# digits.net
KiCad netlist of a schematic drawn in EAGLE
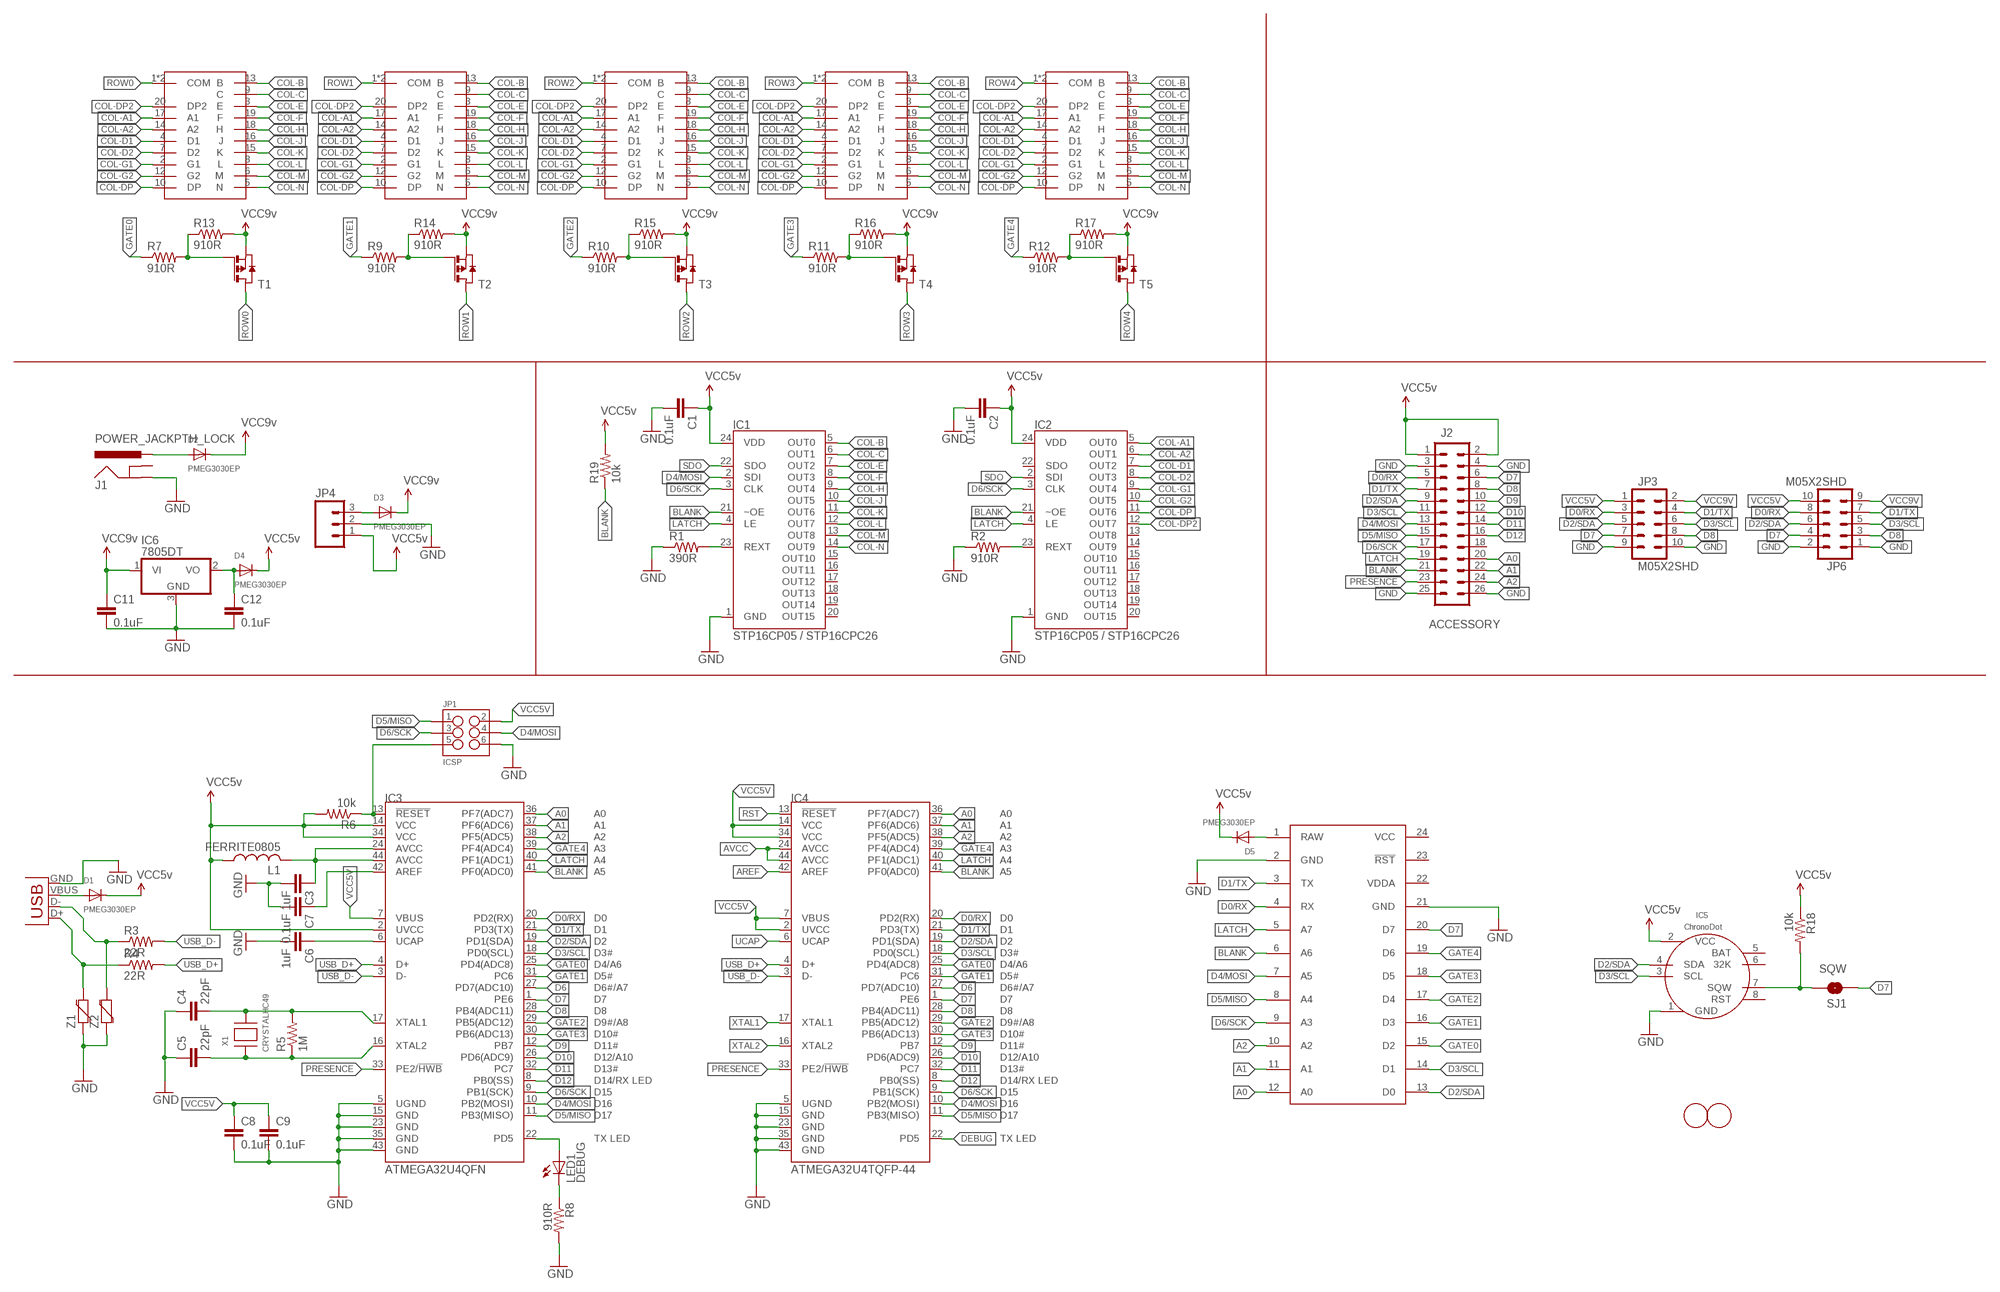
[diagram p0: schematic, sheet 1]

(export (version "E")
  (design (tool "Eeschema 10.0.6"))
  (components
    (comp (ref "C1")
      (value "0.1uF")
      (footprint "eagle-import:0805")
      (fields (field (name "PARTNO") "C0805C104K5RACTU"))
      (libsource (lib "eagle-import") (part "CAP0805"))
    )
    (comp (ref "C2")
      (value "0.1uF")
      (footprint "eagle-import:0805")
      (fields (field (name "PARTNO") "C0805C104K5RACTU"))
      (libsource (lib "eagle-import") (part "CAP0805"))
    )
    (comp (ref "C3")
      (value "1uF")
      (footprint "eagle-import:0805")
      (fields (field (name "PARTNO") "CL21B105KBFNNNE"))
      (libsource (lib "eagle-import") (part "CAP0805"))
    )
    (comp (ref "C4")
      (value "22pF")
      (footprint "eagle-import:0805")
      (fields (field (name "PARTNO") "C0805C220J5GACTU"))
      (libsource (lib "eagle-import") (part "CAP0805"))
    )
    (comp (ref "C5")
      (value "22pF")
      (footprint "eagle-import:0805")
      (fields (field (name "PARTNO") "C0805C220J5GACTU"))
      (libsource (lib "eagle-import") (part "CAP0805"))
    )
    (comp (ref "C6")
      (value "1uF")
      (footprint "eagle-import:0805")
      (fields (field (name "PARTNO") "CL21B105KBFNNNE"))
      (libsource (lib "eagle-import") (part "CAP0805"))
    )
    (comp (ref "C7")
      (value "0.1uF")
      (footprint "eagle-import:0805")
      (fields (field (name "PARTNO") "C0805C104K5RACTU"))
      (libsource (lib "eagle-import") (part "CAP0805"))
    )
    (comp (ref "C8")
      (value "0.1uF")
      (footprint "eagle-import:0805")
      (fields (field (name "PARTNO") "C0805C104K5RACTU"))
      (libsource (lib "eagle-import") (part "CAP0805"))
    )
    (comp (ref "C9")
      (value "0.1uF")
      (footprint "eagle-import:0805")
      (fields (field (name "PARTNO") "C0805C104K5RACTU"))
      (libsource (lib "eagle-import") (part "CAP0805"))
    )
    (comp (ref "C11")
      (value "0.1uF")
      (footprint "eagle-import:0805")
      (fields (field (name "PARTNO") "C0805C104K5RACTU"))
      (libsource (lib "eagle-import") (part "CAP0805"))
    )
    (comp (ref "C12")
      (value "0.1uF")
      (footprint "eagle-import:0805")
      (fields (field (name "PARTNO") "C0805C104K5RACTU"))
      (libsource (lib "eagle-import") (part "CAP0805"))
    )
    (comp (ref "CORE")
      (value "Spark Core")
      (footprint "eagle-import:SPARK_CORE")
      (libsource (lib "eagle-import") (part "SPARK_CORECORE"))
    )
    (comp (ref "D1")
      (value "PMEG3030EP")
      (footprint "eagle-import:SOD-128")
      (fields (field (name "PARTNO") "PMEG3030EP-115"))
      (libsource (lib "eagle-import") (part "DIODESOD-128"))
    )
    (comp (ref "D2")
      (value "PMEG3030EP")
      (footprint "eagle-import:SOD-128")
      (fields (field (name "PARTNO") "PMEG3030EP-115"))
      (libsource (lib "eagle-import") (part "DIODESOD-128"))
    )
    (comp (ref "D3")
      (value "PMEG3030EP")
      (footprint "eagle-import:SOD-128")
      (fields (field (name "PARTNO") "PMEG3030EP-115"))
      (libsource (lib "eagle-import") (part "DIODESOD-128"))
    )
    (comp (ref "D4")
      (value "PMEG3030EP")
      (footprint "eagle-import:SOD-128")
      (fields (field (name "PARTNO") "PMEG3030EP-115"))
      (libsource (lib "eagle-import") (part "DIODESOD-128"))
    )
    (comp (ref "D5")
      (value "PMEG3030EP")
      (footprint "eagle-import:SOD-128")
      (fields (field (name "PARTNO") "PMEG3030EP-115"))
      (libsource (lib "eagle-import") (part "DIODESOD-128"))
    )
    (comp (ref "IC1")
      (value "STP16CP05 / STP16CPC26")
      (footprint "eagle-import:SO-24DW")
      (fields (field (name "PARTNO") "STP16CPC26MTR"))
      (libsource (lib "eagle-import") (part "STP16CP05"))
    )
    (comp (ref "IC2")
      (value "STP16CP05 / STP16CPC26")
      (footprint "eagle-import:SO-24DW")
      (fields (field (name "PARTNO") "STP16CPC26MTR"))
      (libsource (lib "eagle-import") (part "STP16CP05"))
    )
    (comp (ref "IC3")
      (value "ATMEGA32U4QFN")
      (footprint "eagle-import:QFN-44")
      (fields (field (name "PARTNO") "ATMEGA32U4-MUR"))
      (libsource (lib "eagle-import") (part "ATMEGA32U4QFN"))
    )
    (comp (ref "IC4")
      (value "ATMEGA32U4TQFP-44")
      (footprint "eagle-import:TQFP44")
      (fields (field (name "PARTNO") "ATMEGA32U4-AU"))
      (libsource (lib "eagle-import") (part "ATMEGA32U4TQFP-44"))
    )
    (comp (ref "IC5")
      (value "CHRONODOT")
      (footprint "eagle-import:CHRONODOT")
      (libsource (lib "eagle-import") (part "CHRONODOT"))
    )
    (comp (ref "IC6")
      (value "7805DT")
      (footprint "eagle-import:TO252")
      (libsource (lib "eagle-import") (part "78DT05"))
    )
    (comp (ref "J1")
      (value "POWER_JACKPTH_LOCK")
      (footprint "eagle-import:POWER_JACK_PTH_LOCK")
      (fields (field (name "PARTNO") "PJ-202A"))
      (libsource (lib "eagle-import") (part "POWER_JACKPTH_LOCK"))
    )
    (comp (ref "J2")
      (value "ACCESSORY")
      (footprint "eagle-import:2X13")
      (fields (field (name "PARTNO") "SFH11-PBPC-D13-ST-BK"))
      (libsource (lib "eagle-import") (part "HEADER-M26"))
    )
    (comp (ref "JP1")
      (value "ICSP")
      (footprint "eagle-import:2X3-NS")
      (fields (field (name "PARTNO") "M20-9980346"))
      (libsource (lib "eagle-import") (part "M03X2NO_SILK"))
    )
    (comp (ref "JP2")
      (value "USBSMD")
      (footprint "eagle-import:USB-MINIB")
      (fields (field (name "PARTNO") "690-005-299-043"))
      (libsource (lib "eagle-import") (part "USBSMD"))
    )
    (comp (ref "JP3")
      (value "M05X2SHD")
      (footprint "eagle-import:2X5-SHROUDED")
      (fields (field (name "PARTNO") "302-S101"))
      (libsource (lib "eagle-import") (part "M05X2SHD"))
    )
    (comp (ref "JP4")
      (value "M03LOCK")
      (footprint "eagle-import:1X03_LOCK")
      (libsource (lib "eagle-import") (part "M03LOCK"))
    )
    (comp (ref "JP6")
      (value "M05X2SHD")
      (footprint "eagle-import:2X5-SHROUDED")
      (fields (field (name "PARTNO") "302-S101"))
      (libsource (lib "eagle-import") (part "M05X2SHD"))
    )
    (comp (ref "L1")
      (value "FERRITE0805")
      (footprint "eagle-import:0805")
      (fields (field (name "PARTNO") "CIM21J601NE"))
      (libsource (lib "eagle-import") (part "FERRITE0805"))
    )
    (comp (ref "LED1")
      (value "DEBUG")
      (footprint "eagle-import:CHIP-LED0805")
      (fields (field (name "PARTNO") "LG R971-KN-1"))
      (libsource (lib "eagle-import") (part "LEDCHIP-LED0805"))
    )
    (comp (ref "R1")
      (value "390R")
      (footprint "eagle-import:0805")
      (fields (field (name "PARTNO") "RC0805FR-07390RL"))
      (libsource (lib "eagle-import") (part "RESISTOR0805-RES"))
    )
    (comp (ref "R2")
      (value "910R")
      (footprint "eagle-import:0805")
      (fields (field (name "PARTNO") "MCR10ERTF9100"))
      (libsource (lib "eagle-import") (part "RESISTOR0805-RES"))
    )
    (comp (ref "R3")
      (value "22R")
      (footprint "eagle-import:0805")
      (fields (field (name "PARTNO") "RC0805FR-0722RL"))
      (libsource (lib "eagle-import") (part "RESISTOR0805-RES"))
    )
    (comp (ref "R4")
      (value "22R")
      (footprint "eagle-import:0805")
      (fields (field (name "PARTNO") "RC0805FR-0722RL"))
      (libsource (lib "eagle-import") (part "RESISTOR0805-RES"))
    )
    (comp (ref "R5")
      (value "1M")
      (footprint "eagle-import:0805")
      (fields (field (name "PARTNO") "RC0805FR-071ML"))
      (libsource (lib "eagle-import") (part "RESISTOR0805-RES"))
    )
    (comp (ref "R6")
      (value "10k")
      (footprint "eagle-import:0805")
      (fields (field (name "PARTNO") "RC0805JR-0710KL"))
      (libsource (lib "eagle-import") (part "RESISTOR0805-RES"))
    )
    (comp (ref "R7")
      (value "910R")
      (footprint "eagle-import:0805")
      (fields (field (name "PARTNO") "MCR10ERTF9100"))
      (libsource (lib "eagle-import") (part "RESISTOR0805-RES"))
    )
    (comp (ref "R8")
      (value "910R")
      (footprint "eagle-import:0805")
      (fields (field (name "PARTNO") "MCR10ERTF9100"))
      (libsource (lib "eagle-import") (part "RESISTOR0805-RES"))
    )
    (comp (ref "R9")
      (value "910R")
      (footprint "eagle-import:0805")
      (fields (field (name "PARTNO") "MCR10ERTF9100"))
      (libsource (lib "eagle-import") (part "RESISTOR0805-RES"))
    )
    (comp (ref "R10")
      (value "910R")
      (footprint "eagle-import:0805")
      (fields (field (name "PARTNO") "MCR10ERTF9100"))
      (libsource (lib "eagle-import") (part "RESISTOR0805-RES"))
    )
    (comp (ref "R11")
      (value "910R")
      (footprint "eagle-import:0805")
      (fields (field (name "PARTNO") "MCR10ERTF9100"))
      (libsource (lib "eagle-import") (part "RESISTOR0805-RES"))
    )
    (comp (ref "R12")
      (value "910R")
      (footprint "eagle-import:0805")
      (fields (field (name "PARTNO") "MCR10ERTF9100"))
      (libsource (lib "eagle-import") (part "RESISTOR0805-RES"))
    )
    (comp (ref "R13")
      (value "910R")
      (footprint "eagle-import:0805")
      (fields (field (name "PARTNO") "MCR10ERTF9100"))
      (libsource (lib "eagle-import") (part "RESISTOR0805-RES"))
    )
    (comp (ref "R14")
      (value "910R")
      (footprint "eagle-import:0805")
      (fields (field (name "PARTNO") "MCR10ERTF9100"))
      (libsource (lib "eagle-import") (part "RESISTOR0805-RES"))
    )
    (comp (ref "R15")
      (value "910R")
      (footprint "eagle-import:0805")
      (fields (field (name "PARTNO") "MCR10ERTF9100"))
      (libsource (lib "eagle-import") (part "RESISTOR0805-RES"))
    )
    (comp (ref "R16")
      (value "910R")
      (footprint "eagle-import:0805")
      (fields (field (name "PARTNO") "MCR10ERTF9100"))
      (libsource (lib "eagle-import") (part "RESISTOR0805-RES"))
    )
    (comp (ref "R17")
      (value "910R")
      (footprint "eagle-import:0805")
      (fields (field (name "PARTNO") "MCR10ERTF9100"))
      (libsource (lib "eagle-import") (part "RESISTOR0805-RES"))
    )
    (comp (ref "R18")
      (value "10k")
      (footprint "eagle-import:0805")
      (fields (field (name "PARTNO") "RC0805JR-0710KL"))
      (libsource (lib "eagle-import") (part "RESISTOR0805-RES"))
    )
    (comp (ref "R19")
      (value "10k")
      (footprint "eagle-import:0805")
      (libsource (lib "eagle-import") (part "RESISTOR0805-RES"))
    )
    (comp (ref "SEG1")
      (value "BL-S230X-12")
      (footprint "eagle-import:BL-S230X-12")
      (libsource (lib "eagle-import") (part "BL-S230X-12"))
    )
    (comp (ref "SEG2")
      (value "BL-S230X-12")
      (footprint "eagle-import:BL-S230X-12")
      (libsource (lib "eagle-import") (part "BL-S230X-12"))
    )
    (comp (ref "SEG3")
      (value "BL-S230X-12")
      (footprint "eagle-import:BL-S230X-12")
      (libsource (lib "eagle-import") (part "BL-S230X-12"))
    )
    (comp (ref "SEG4")
      (value "BL-S230X-12")
      (footprint "eagle-import:BL-S230X-12")
      (libsource (lib "eagle-import") (part "BL-S230X-12"))
    )
    (comp (ref "SEG5")
      (value "BL-S230X-12")
      (footprint "eagle-import:BL-S230X-12")
      (libsource (lib "eagle-import") (part "BL-S230X-12"))
    )
    (comp (ref "SJ1")
      (value "SQW")
      (footprint "eagle-import:SJ_2S-NO")
      (libsource (lib "eagle-import") (part "SOLDERJUMPERNO"))
    )
    (comp (ref "T1")
      (value "PMOSSOT23")
      (footprint "eagle-import:SOT-23")
      (fields (field (name "PARTNO") "FDN352AP"))
      (libsource (lib "eagle-import") (part "PMOSSOT23"))
    )
    (comp (ref "T2")
      (value "PMOSSOT23")
      (footprint "eagle-import:SOT-23")
      (fields (field (name "PARTNO") "FDN352AP"))
      (libsource (lib "eagle-import") (part "PMOSSOT23"))
    )
    (comp (ref "T3")
      (value "PMOSSOT23")
      (footprint "eagle-import:SOT-23")
      (fields (field (name "PARTNO") "FDN352AP"))
      (libsource (lib "eagle-import") (part "PMOSSOT23"))
    )
    (comp (ref "T4")
      (value "PMOSSOT23")
      (footprint "eagle-import:SOT-23")
      (fields (field (name "PARTNO") "FDN352AP"))
      (libsource (lib "eagle-import") (part "PMOSSOT23"))
    )
    (comp (ref "T5")
      (value "PMOSSOT23")
      (footprint "eagle-import:SOT-23")
      (fields (field (name "PARTNO") "FDN352AP"))
      (libsource (lib "eagle-import") (part "PMOSSOT23"))
    )
    (comp (ref "U$1")
      (value "FIDUCIAL")
      (footprint "eagle-import:FIDUCIAL_1MM")
      (libsource (lib "eagle-import") (part "FIDUCIAL"))
    )
    (comp (ref "U$2")
      (value "FIDUCIAL")
      (footprint "eagle-import:FIDUCIAL_1MM")
      (libsource (lib "eagle-import") (part "FIDUCIAL"))
    )
    (comp (ref "X1")
      (value "CRYSTALHC49")
      (footprint "eagle-import:HC49")
      (fields (field (name "PARTNO") "9C-16.000MAAJ-T"))
      (libsource (lib "eagle-import") (part "CRYSTALHC49"))
    )
    (comp (ref "Z1")
      (value "VARISTOR-0603")
      (footprint "eagle-import:0603-RES")
      (fields (field (name "PARTNO") "CG0603MLC-05E"))
      (libsource (lib "eagle-import") (part "VARISTOR-0603"))
    )
    (comp (ref "Z2")
      (value "VARISTOR-0603")
      (footprint "eagle-import:0603-RES")
      (fields (field (name "PARTNO") "CG0603MLC-05E"))
      (libsource (lib "eagle-import") (part "VARISTOR-0603"))
    )
  )
  (nets
    (net (code "1") (name "/VCC") (class "Default")
      (node (ref "CORE") (pin "24") (pinfunction "VCC_24") (pintype "power_in"))
    )
    (net (code "2") (name "/VDDA") (class "Default")
      (node (ref "CORE") (pin "22") (pinfunction "VDDA_22") (pintype "power_in"))
    )
    (net (code "3") (name "A0") (class "Default")
      (node (ref "CORE") (pin "12") (pinfunction "A0_12") (pintype "bidirectional"))
      (node (ref "IC3") (pin "36") (pinfunction "PF7(ADC7)_36") (pintype "bidirectional"))
      (node (ref "IC4") (pin "36") (pinfunction "PF7(ADC7)_36") (pintype "bidirectional"))
      (node (ref "J2") (pin "20") (pinfunction "20_20") (pintype "passive"))
    )
    (net (code "4") (name "A1") (class "Default")
      (node (ref "CORE") (pin "11") (pinfunction "A1_11") (pintype "bidirectional"))
      (node (ref "IC3") (pin "37") (pinfunction "PF6(ADC6)_37") (pintype "bidirectional"))
      (node (ref "IC4") (pin "37") (pinfunction "PF6(ADC6)_37") (pintype "bidirectional"))
      (node (ref "J2") (pin "22") (pinfunction "22_22") (pintype "passive"))
    )
    (net (code "5") (name "A2") (class "Default")
      (node (ref "CORE") (pin "10") (pinfunction "A2_10") (pintype "bidirectional"))
      (node (ref "IC3") (pin "38") (pinfunction "PF5(ADC5)_38") (pintype "bidirectional"))
      (node (ref "IC4") (pin "38") (pinfunction "PF5(ADC5)_38") (pintype "bidirectional"))
      (node (ref "J2") (pin "24") (pinfunction "24_24") (pintype "passive"))
    )
    (net (code "6") (name "AREF") (class "Default")
      (node (ref "C7") (pin "1") (pinfunction "1_1") (pintype "passive"))
      (node (ref "IC3") (pin "42") (pinfunction "AREF_42") (pintype "bidirectional"))
      (node (ref "IC4") (pin "42") (pinfunction "AREF_42") (pintype "bidirectional"))
    )
    (net (code "7") (name "AVCC") (class "Default")
      (node (ref "C3") (pin "1") (pinfunction "1_1") (pintype "passive"))
      (node (ref "IC3") (pin "24") (pinfunction "AVCC_24") (pintype "bidirectional"))
      (node (ref "IC3") (pin "44") (pinfunction "AVCC_44") (pintype "bidirectional"))
      (node (ref "IC4") (pin "24") (pinfunction "AVCC_24") (pintype "bidirectional"))
      (node (ref "IC4") (pin "44") (pinfunction "AVCC_44") (pintype "bidirectional"))
      (node (ref "L1") (pin "2") (pinfunction "2_2") (pintype "passive"))
    )
    (net (code "8") (name "BLANK") (class "Default")
      (node (ref "CORE") (pin "6") (pinfunction "A6_6") (pintype "bidirectional"))
      (node (ref "IC1") (pin "21") (pinfunction "~{OE}_21") (pintype "bidirectional"))
      (node (ref "IC2") (pin "21") (pinfunction "~{OE}_21") (pintype "bidirectional"))
      (node (ref "IC3") (pin "41") (pinfunction "PF0(ADC0)_41") (pintype "bidirectional"))
      (node (ref "IC4") (pin "41") (pinfunction "PF0(ADC0)_41") (pintype "bidirectional"))
      (node (ref "J2") (pin "21") (pinfunction "21_21") (pintype "passive"))
      (node (ref "R19") (pin "1") (pinfunction "1_1") (pintype "passive"))
    )
    (net (code "9") (name "COL-A1") (class "Default")
      (node (ref "IC2") (pin "5") (pinfunction "OUT0_5") (pintype "bidirectional"))
      (node (ref "SEG1") (pin "17") (pinfunction "A1_17") (pintype "bidirectional"))
      (node (ref "SEG2") (pin "17") (pinfunction "A1_17") (pintype "bidirectional"))
      (node (ref "SEG3") (pin "17") (pinfunction "A1_17") (pintype "bidirectional"))
      (node (ref "SEG4") (pin "17") (pinfunction "A1_17") (pintype "bidirectional"))
      (node (ref "SEG5") (pin "17") (pinfunction "A1_17") (pintype "bidirectional"))
    )
    (net (code "10") (name "COL-A2") (class "Default")
      (node (ref "IC2") (pin "6") (pinfunction "OUT1_6") (pintype "bidirectional"))
      (node (ref "SEG1") (pin "14") (pinfunction "A2_14") (pintype "bidirectional"))
      (node (ref "SEG2") (pin "14") (pinfunction "A2_14") (pintype "bidirectional"))
      (node (ref "SEG3") (pin "14") (pinfunction "A2_14") (pintype "bidirectional"))
      (node (ref "SEG4") (pin "14") (pinfunction "A2_14") (pintype "bidirectional"))
      (node (ref "SEG5") (pin "14") (pinfunction "A2_14") (pintype "bidirectional"))
    )
    (net (code "11") (name "COL-B") (class "Default")
      (node (ref "IC1") (pin "5") (pinfunction "OUT0_5") (pintype "bidirectional"))
      (node (ref "SEG1") (pin "13") (pinfunction "B_13") (pintype "bidirectional"))
      (node (ref "SEG2") (pin "13") (pinfunction "B_13") (pintype "bidirectional"))
      (node (ref "SEG3") (pin "13") (pinfunction "B_13") (pintype "bidirectional"))
      (node (ref "SEG4") (pin "13") (pinfunction "B_13") (pintype "bidirectional"))
      (node (ref "SEG5") (pin "13") (pinfunction "B_13") (pintype "bidirectional"))
    )
    (net (code "12") (name "COL-C") (class "Default")
      (node (ref "IC1") (pin "6") (pinfunction "OUT1_6") (pintype "bidirectional"))
      (node (ref "SEG1") (pin "9") (pinfunction "C_9") (pintype "bidirectional"))
      (node (ref "SEG2") (pin "9") (pinfunction "C_9") (pintype "bidirectional"))
      (node (ref "SEG3") (pin "9") (pinfunction "C_9") (pintype "bidirectional"))
      (node (ref "SEG4") (pin "9") (pinfunction "C_9") (pintype "bidirectional"))
      (node (ref "SEG5") (pin "9") (pinfunction "C_9") (pintype "bidirectional"))
    )
    (net (code "13") (name "COL-D1") (class "Default")
      (node (ref "IC2") (pin "7") (pinfunction "OUT2_7") (pintype "bidirectional"))
      (node (ref "SEG1") (pin "4") (pinfunction "D1_4") (pintype "bidirectional"))
      (node (ref "SEG2") (pin "4") (pinfunction "D1_4") (pintype "bidirectional"))
      (node (ref "SEG3") (pin "4") (pinfunction "D1_4") (pintype "bidirectional"))
      (node (ref "SEG4") (pin "4") (pinfunction "D1_4") (pintype "bidirectional"))
      (node (ref "SEG5") (pin "4") (pinfunction "D1_4") (pintype "bidirectional"))
    )
    (net (code "14") (name "COL-D2") (class "Default")
      (node (ref "IC2") (pin "8") (pinfunction "OUT3_8") (pintype "bidirectional"))
      (node (ref "SEG1") (pin "7") (pinfunction "D2_7") (pintype "bidirectional"))
      (node (ref "SEG2") (pin "7") (pinfunction "D2_7") (pintype "bidirectional"))
      (node (ref "SEG3") (pin "7") (pinfunction "D2_7") (pintype "bidirectional"))
      (node (ref "SEG4") (pin "7") (pinfunction "D2_7") (pintype "bidirectional"))
      (node (ref "SEG5") (pin "7") (pinfunction "D2_7") (pintype "bidirectional"))
    )
    (net (code "15") (name "COL-DP") (class "Default")
      (node (ref "IC2") (pin "11") (pinfunction "OUT6_11") (pintype "bidirectional"))
      (node (ref "SEG1") (pin "10") (pinfunction "DP_10") (pintype "bidirectional"))
      (node (ref "SEG2") (pin "10") (pinfunction "DP_10") (pintype "bidirectional"))
      (node (ref "SEG3") (pin "10") (pinfunction "DP_10") (pintype "bidirectional"))
      (node (ref "SEG4") (pin "10") (pinfunction "DP_10") (pintype "bidirectional"))
      (node (ref "SEG5") (pin "10") (pinfunction "DP_10") (pintype "bidirectional"))
    )
    (net (code "16") (name "COL-DP2") (class "Default")
      (node (ref "IC2") (pin "12") (pinfunction "OUT7_12") (pintype "bidirectional"))
      (node (ref "SEG1") (pin "20") (pinfunction "DP2_20") (pintype "bidirectional"))
      (node (ref "SEG2") (pin "20") (pinfunction "DP2_20") (pintype "bidirectional"))
      (node (ref "SEG3") (pin "20") (pinfunction "DP2_20") (pintype "bidirectional"))
      (node (ref "SEG4") (pin "20") (pinfunction "DP2_20") (pintype "bidirectional"))
      (node (ref "SEG5") (pin "20") (pinfunction "DP2_20") (pintype "bidirectional"))
    )
    (net (code "17") (name "COL-E") (class "Default")
      (node (ref "IC1") (pin "7") (pinfunction "OUT2_7") (pintype "bidirectional"))
      (node (ref "SEG1") (pin "3") (pinfunction "E_3") (pintype "bidirectional"))
      (node (ref "SEG2") (pin "3") (pinfunction "E_3") (pintype "bidirectional"))
      (node (ref "SEG3") (pin "3") (pinfunction "E_3") (pintype "bidirectional"))
      (node (ref "SEG4") (pin "3") (pinfunction "E_3") (pintype "bidirectional"))
      (node (ref "SEG5") (pin "3") (pinfunction "E_3") (pintype "bidirectional"))
    )
    (net (code "18") (name "COL-F") (class "Default")
      (node (ref "IC1") (pin "8") (pinfunction "OUT3_8") (pintype "bidirectional"))
      (node (ref "SEG1") (pin "19") (pinfunction "F_19") (pintype "bidirectional"))
      (node (ref "SEG2") (pin "19") (pinfunction "F_19") (pintype "bidirectional"))
      (node (ref "SEG3") (pin "19") (pinfunction "F_19") (pintype "bidirectional"))
      (node (ref "SEG4") (pin "19") (pinfunction "F_19") (pintype "bidirectional"))
      (node (ref "SEG5") (pin "19") (pinfunction "F_19") (pintype "bidirectional"))
    )
    (net (code "19") (name "COL-G1") (class "Default")
      (node (ref "IC2") (pin "9") (pinfunction "OUT4_9") (pintype "bidirectional"))
      (node (ref "SEG1") (pin "2") (pinfunction "G1_2") (pintype "bidirectional"))
      (node (ref "SEG2") (pin "2") (pinfunction "G1_2") (pintype "bidirectional"))
      (node (ref "SEG3") (pin "2") (pinfunction "G1_2") (pintype "bidirectional"))
      (node (ref "SEG4") (pin "2") (pinfunction "G1_2") (pintype "bidirectional"))
      (node (ref "SEG5") (pin "2") (pinfunction "G1_2") (pintype "bidirectional"))
    )
    (net (code "20") (name "COL-G2") (class "Default")
      (node (ref "IC2") (pin "10") (pinfunction "OUT5_10") (pintype "bidirectional"))
      (node (ref "SEG1") (pin "12") (pinfunction "G2_12") (pintype "bidirectional"))
      (node (ref "SEG2") (pin "12") (pinfunction "G2_12") (pintype "bidirectional"))
      (node (ref "SEG3") (pin "12") (pinfunction "G2_12") (pintype "bidirectional"))
      (node (ref "SEG4") (pin "12") (pinfunction "G2_12") (pintype "bidirectional"))
      (node (ref "SEG5") (pin "12") (pinfunction "G2_12") (pintype "bidirectional"))
    )
    (net (code "21") (name "COL-H") (class "Default")
      (node (ref "IC1") (pin "9") (pinfunction "OUT4_9") (pintype "bidirectional"))
      (node (ref "SEG1") (pin "18") (pinfunction "H_18") (pintype "bidirectional"))
      (node (ref "SEG2") (pin "18") (pinfunction "H_18") (pintype "bidirectional"))
      (node (ref "SEG3") (pin "18") (pinfunction "H_18") (pintype "bidirectional"))
      (node (ref "SEG4") (pin "18") (pinfunction "H_18") (pintype "bidirectional"))
      (node (ref "SEG5") (pin "18") (pinfunction "H_18") (pintype "bidirectional"))
    )
    (net (code "22") (name "COL-J") (class "Default")
      (node (ref "IC1") (pin "10") (pinfunction "OUT5_10") (pintype "bidirectional"))
      (node (ref "SEG1") (pin "16") (pinfunction "J_16") (pintype "bidirectional"))
      (node (ref "SEG2") (pin "16") (pinfunction "J_16") (pintype "bidirectional"))
      (node (ref "SEG3") (pin "16") (pinfunction "J_16") (pintype "bidirectional"))
      (node (ref "SEG4") (pin "16") (pinfunction "J_16") (pintype "bidirectional"))
      (node (ref "SEG5") (pin "16") (pinfunction "J_16") (pintype "bidirectional"))
    )
    (net (code "23") (name "COL-K") (class "Default")
      (node (ref "IC1") (pin "11") (pinfunction "OUT6_11") (pintype "bidirectional"))
      (node (ref "SEG1") (pin "15") (pinfunction "K_15") (pintype "bidirectional"))
      (node (ref "SEG2") (pin "15") (pinfunction "K_15") (pintype "bidirectional"))
      (node (ref "SEG3") (pin "15") (pinfunction "K_15") (pintype "bidirectional"))
      (node (ref "SEG4") (pin "15") (pinfunction "K_15") (pintype "bidirectional"))
      (node (ref "SEG5") (pin "15") (pinfunction "K_15") (pintype "bidirectional"))
    )
    (net (code "24") (name "COL-L") (class "Default")
      (node (ref "IC1") (pin "12") (pinfunction "OUT7_12") (pintype "bidirectional"))
      (node (ref "SEG1") (pin "8") (pinfunction "L_8") (pintype "bidirectional"))
      (node (ref "SEG2") (pin "8") (pinfunction "L_8") (pintype "bidirectional"))
      (node (ref "SEG3") (pin "8") (pinfunction "L_8") (pintype "bidirectional"))
      (node (ref "SEG4") (pin "8") (pinfunction "L_8") (pintype "bidirectional"))
      (node (ref "SEG5") (pin "8") (pinfunction "L_8") (pintype "bidirectional"))
    )
    (net (code "25") (name "COL-M") (class "Default")
      (node (ref "IC1") (pin "13") (pinfunction "OUT8_13") (pintype "bidirectional"))
      (node (ref "SEG1") (pin "6") (pinfunction "M_6") (pintype "bidirectional"))
      (node (ref "SEG2") (pin "6") (pinfunction "M_6") (pintype "bidirectional"))
      (node (ref "SEG3") (pin "6") (pinfunction "M_6") (pintype "bidirectional"))
      (node (ref "SEG4") (pin "6") (pinfunction "M_6") (pintype "bidirectional"))
      (node (ref "SEG5") (pin "6") (pinfunction "M_6") (pintype "bidirectional"))
    )
    (net (code "26") (name "COL-N") (class "Default")
      (node (ref "IC1") (pin "14") (pinfunction "OUT9_14") (pintype "bidirectional"))
      (node (ref "SEG1") (pin "5") (pinfunction "N_5") (pintype "bidirectional"))
      (node (ref "SEG2") (pin "5") (pinfunction "N_5") (pintype "bidirectional"))
      (node (ref "SEG3") (pin "5") (pinfunction "N_5") (pintype "bidirectional"))
      (node (ref "SEG4") (pin "5") (pinfunction "N_5") (pintype "bidirectional"))
      (node (ref "SEG5") (pin "5") (pinfunction "N_5") (pintype "bidirectional"))
    )
    (net (code "27") (name "D0{slash}RX") (class "Default")
      (node (ref "CORE") (pin "4") (pinfunction "RX_4") (pintype "bidirectional"))
      (node (ref "IC3") (pin "20") (pinfunction "PD2(RX)_20") (pintype "bidirectional"))
      (node (ref "IC4") (pin "20") (pinfunction "PD2(RX)_20") (pintype "bidirectional"))
      (node (ref "J2") (pin "5") (pinfunction "5_5") (pintype "passive"))
      (node (ref "JP3") (pin "3") (pinfunction "3_3") (pintype "passive"))
      (node (ref "JP6") (pin "8") (pinfunction "8_8") (pintype "passive"))
    )
    (net (code "28") (name "D1{slash}TX") (class "Default")
      (node (ref "CORE") (pin "3") (pinfunction "TX_3") (pintype "bidirectional"))
      (node (ref "IC3") (pin "21") (pinfunction "PD3(TX)_21") (pintype "bidirectional"))
      (node (ref "IC4") (pin "21") (pinfunction "PD3(TX)_21") (pintype "bidirectional"))
      (node (ref "J2") (pin "7") (pinfunction "7_7") (pintype "passive"))
      (node (ref "JP3") (pin "4") (pinfunction "4_4") (pintype "passive"))
      (node (ref "JP6") (pin "7") (pinfunction "7_7") (pintype "passive"))
    )
    (net (code "29") (name "D2{slash}SDA") (class "Default")
      (node (ref "CORE") (pin "13") (pinfunction "D0_13") (pintype "bidirectional"))
      (node (ref "IC3") (pin "19") (pinfunction "PD1(SDA)_19") (pintype "bidirectional"))
      (node (ref "IC4") (pin "19") (pinfunction "PD1(SDA)_19") (pintype "bidirectional"))
      (node (ref "IC5") (pin "4") (pinfunction "SDA_4") (pintype "bidirectional"))
      (node (ref "J2") (pin "9") (pinfunction "9_9") (pintype "passive"))
      (node (ref "JP3") (pin "5") (pinfunction "5_5") (pintype "passive"))
      (node (ref "JP6") (pin "6") (pinfunction "6_6") (pintype "passive"))
    )
    (net (code "30") (name "D3{slash}SCL") (class "Default")
      (node (ref "CORE") (pin "14") (pinfunction "D1_14") (pintype "bidirectional"))
      (node (ref "IC3") (pin "18") (pinfunction "PD0(SCL)_18") (pintype "bidirectional"))
      (node (ref "IC4") (pin "18") (pinfunction "PD0(SCL)_18") (pintype "bidirectional"))
      (node (ref "IC5") (pin "3") (pinfunction "SCL_3") (pintype "bidirectional"))
      (node (ref "J2") (pin "11") (pinfunction "11_11") (pintype "passive"))
      (node (ref "JP3") (pin "6") (pinfunction "6_6") (pintype "passive"))
      (node (ref "JP6") (pin "5") (pinfunction "5_5") (pintype "passive"))
    )
    (net (code "31") (name "D4{slash}MOSI") (class "Default")
      (node (ref "CORE") (pin "7") (pinfunction "A5_7") (pintype "bidirectional"))
      (node (ref "IC1") (pin "2") (pinfunction "SDI_2") (pintype "bidirectional"))
      (node (ref "IC3") (pin "10") (pinfunction "PB2(MOSI)_10") (pintype "bidirectional"))
      (node (ref "IC4") (pin "10") (pinfunction "PB2(MOSI)_10") (pintype "bidirectional"))
      (node (ref "J2") (pin "13") (pinfunction "13_13") (pintype "passive"))
      (node (ref "JP1") (pin "4") (pinfunction "4_4") (pintype "bidirectional"))
    )
    (net (code "32") (name "D5{slash}MISO") (class "Default")
      (node (ref "CORE") (pin "8") (pinfunction "A4_8") (pintype "bidirectional"))
      (node (ref "IC3") (pin "11") (pinfunction "PB3(MISO)_11") (pintype "bidirectional"))
      (node (ref "IC4") (pin "11") (pinfunction "PB3(MISO)_11") (pintype "bidirectional"))
      (node (ref "J2") (pin "15") (pinfunction "15_15") (pintype "passive"))
      (node (ref "JP1") (pin "1") (pinfunction "1_1") (pintype "bidirectional"))
    )
    (net (code "33") (name "D6") (class "Default")
      (node (ref "IC3") (pin "27") (pinfunction "PD7(ADC10)_27") (pintype "bidirectional"))
      (node (ref "IC4") (pin "27") (pinfunction "PD7(ADC10)_27") (pintype "bidirectional"))
    )
    (net (code "34") (name "D6{slash}SCK") (class "Default")
      (node (ref "CORE") (pin "9") (pinfunction "A3_9") (pintype "bidirectional"))
      (node (ref "IC1") (pin "3") (pinfunction "CLK_3") (pintype "bidirectional"))
      (node (ref "IC2") (pin "3") (pinfunction "CLK_3") (pintype "bidirectional"))
      (node (ref "IC3") (pin "9") (pinfunction "PB1(SCK)_9") (pintype "bidirectional"))
      (node (ref "IC4") (pin "9") (pinfunction "PB1(SCK)_9") (pintype "bidirectional"))
      (node (ref "J2") (pin "17") (pinfunction "17_17") (pintype "passive"))
      (node (ref "JP1") (pin "3") (pinfunction "3_3") (pintype "bidirectional"))
    )
    (net (code "35") (name "D7") (class "Default")
      (node (ref "CORE") (pin "20") (pinfunction "D7_20") (pintype "bidirectional"))
      (node (ref "IC3") (pin "1") (pinfunction "PE6_1") (pintype "bidirectional"))
      (node (ref "IC4") (pin "1") (pinfunction "PE6_1") (pintype "bidirectional"))
      (node (ref "J2") (pin "6") (pinfunction "6_6") (pintype "passive"))
      (node (ref "JP3") (pin "7") (pinfunction "7_7") (pintype "passive"))
      (node (ref "JP6") (pin "4") (pinfunction "4_4") (pintype "passive"))
      (node (ref "SJ1") (pin "1") (pinfunction "1_1") (pintype "passive"))
    )
    (net (code "36") (name "D8") (class "Default")
      (node (ref "IC3") (pin "28") (pinfunction "PB4(ADC11)_28") (pintype "bidirectional"))
      (node (ref "IC4") (pin "28") (pinfunction "PB4(ADC11)_28") (pintype "bidirectional"))
      (node (ref "J2") (pin "8") (pinfunction "8_8") (pintype "passive"))
      (node (ref "JP3") (pin "8") (pinfunction "8_8") (pintype "passive"))
      (node (ref "JP6") (pin "3") (pinfunction "3_3") (pintype "passive"))
    )
    (net (code "37") (name "D9") (class "Default")
      (node (ref "IC3") (pin "12") (pinfunction "PB7_12") (pintype "bidirectional"))
      (node (ref "IC4") (pin "12") (pinfunction "PB7_12") (pintype "bidirectional"))
      (node (ref "J2") (pin "10") (pinfunction "10_10") (pintype "passive"))
    )
    (net (code "38") (name "D10") (class "Default")
      (node (ref "IC3") (pin "26") (pinfunction "PD6(ADC9)_26") (pintype "bidirectional"))
      (node (ref "IC4") (pin "26") (pinfunction "PD6(ADC9)_26") (pintype "bidirectional"))
      (node (ref "J2") (pin "12") (pinfunction "12_12") (pintype "passive"))
    )
    (net (code "39") (name "D11") (class "Default")
      (node (ref "IC3") (pin "32") (pinfunction "PC7_32") (pintype "bidirectional"))
      (node (ref "IC4") (pin "32") (pinfunction "PC7_32") (pintype "bidirectional"))
      (node (ref "J2") (pin "14") (pinfunction "14_14") (pintype "passive"))
    )
    (net (code "40") (name "D12") (class "Default")
      (node (ref "IC3") (pin "8") (pinfunction "PB0(SS)_8") (pintype "bidirectional"))
      (node (ref "IC4") (pin "8") (pinfunction "PB0(SS)_8") (pintype "bidirectional"))
      (node (ref "J2") (pin "16") (pinfunction "16_16") (pintype "passive"))
    )
    (net (code "41") (name "DEBUG") (class "Default")
      (node (ref "IC3") (pin "22") (pinfunction "PD5_22") (pintype "bidirectional"))
      (node (ref "IC4") (pin "22") (pinfunction "PD5_22") (pintype "bidirectional"))
      (node (ref "LED1") (pin "A") (pinfunction "A_A") (pintype "passive"))
    )
    (net (code "42") (name "GATE0") (class "Default")
      (node (ref "CORE") (pin "15") (pinfunction "D2_15") (pintype "bidirectional"))
      (node (ref "IC3") (pin "25") (pinfunction "PD4(ADC8)_25") (pintype "bidirectional"))
      (node (ref "IC4") (pin "25") (pinfunction "PD4(ADC8)_25") (pintype "bidirectional"))
      (node (ref "R7") (pin "1") (pinfunction "1_1") (pintype "passive"))
    )
    (net (code "43") (name "GATE1") (class "Default")
      (node (ref "CORE") (pin "16") (pinfunction "D3_16") (pintype "bidirectional"))
      (node (ref "IC3") (pin "31") (pinfunction "PC6_31") (pintype "bidirectional"))
      (node (ref "IC4") (pin "31") (pinfunction "PC6_31") (pintype "bidirectional"))
      (node (ref "R9") (pin "1") (pinfunction "1_1") (pintype "passive"))
    )
    (net (code "44") (name "GATE2") (class "Default")
      (node (ref "CORE") (pin "17") (pinfunction "D4_17") (pintype "bidirectional"))
      (node (ref "IC3") (pin "29") (pinfunction "PB5(ADC12)_29") (pintype "bidirectional"))
      (node (ref "IC4") (pin "29") (pinfunction "PB5(ADC12)_29") (pintype "bidirectional"))
      (node (ref "R10") (pin "1") (pinfunction "1_1") (pintype "passive"))
    )
    (net (code "45") (name "GATE3") (class "Default")
      (node (ref "CORE") (pin "18") (pinfunction "D5_18") (pintype "bidirectional"))
      (node (ref "IC3") (pin "30") (pinfunction "PB6(ADC13)_30") (pintype "bidirectional"))
      (node (ref "IC4") (pin "30") (pinfunction "PB6(ADC13)_30") (pintype "bidirectional"))
      (node (ref "R11") (pin "1") (pinfunction "1_1") (pintype "passive"))
    )
    (net (code "46") (name "GATE4") (class "Default")
      (node (ref "CORE") (pin "19") (pinfunction "D6_19") (pintype "bidirectional"))
      (node (ref "IC3") (pin "39") (pinfunction "PF4(ADC4)_39") (pintype "bidirectional"))
      (node (ref "IC4") (pin "39") (pinfunction "PF4(ADC4)_39") (pintype "bidirectional"))
      (node (ref "R12") (pin "1") (pinfunction "1_1") (pintype "passive"))
    )
    (net (code "47") (name "GND") (class "Default")
      (node (ref "C1") (pin "2") (pinfunction "2_2") (pintype "passive"))
      (node (ref "C11") (pin "2") (pinfunction "2_2") (pintype "passive"))
      (node (ref "C12") (pin "2") (pinfunction "2_2") (pintype "passive"))
      (node (ref "C2") (pin "2") (pinfunction "2_2") (pintype "passive"))
      (node (ref "C3") (pin "2") (pinfunction "2_2") (pintype "passive"))
      (node (ref "C4") (pin "1") (pinfunction "1_1") (pintype "passive"))
      (node (ref "C5") (pin "1") (pinfunction "1_1") (pintype "passive"))
      (node (ref "C6") (pin "2") (pinfunction "2_2") (pintype "passive"))
      (node (ref "C7") (pin "2") (pinfunction "2_2") (pintype "passive"))
      (node (ref "C8") (pin "2") (pinfunction "2_2") (pintype "passive"))
      (node (ref "C9") (pin "2") (pinfunction "2_2") (pintype "passive"))
      (node (ref "CORE") (pin "2") (pinfunction "GND_2") (pintype "power_in"))
      (node (ref "CORE") (pin "21") (pinfunction "GND_21") (pintype "power_in"))
      (node (ref "IC1") (pin "1") (pinfunction "GND_1") (pintype "bidirectional"))
      (node (ref "IC2") (pin "1") (pinfunction "GND_1") (pintype "bidirectional"))
      (node (ref "IC3") (pin "15") (pinfunction "GND_15") (pintype "bidirectional"))
      (node (ref "IC3") (pin "23") (pinfunction "GND_23") (pintype "bidirectional"))
      (node (ref "IC3") (pin "35") (pinfunction "GND_35") (pintype "bidirectional"))
      (node (ref "IC3") (pin "43") (pinfunction "GND_43") (pintype "bidirectional"))
      (node (ref "IC3") (pin "5") (pinfunction "UGND_5") (pintype "bidirectional"))
      (node (ref "IC4") (pin "15") (pinfunction "GND_15") (pintype "bidirectional"))
      (node (ref "IC4") (pin "23") (pinfunction "GND_23") (pintype "bidirectional"))
      (node (ref "IC4") (pin "35") (pinfunction "GND_35") (pintype "bidirectional"))
      (node (ref "IC4") (pin "43") (pinfunction "GND_43") (pintype "bidirectional"))
      (node (ref "IC4") (pin "5") (pinfunction "UGND_5") (pintype "bidirectional"))
      (node (ref "IC5") (pin "1") (pinfunction "GND_1") (pintype "bidirectional"))
      (node (ref "IC6") (pin "3") (pinfunction "GND_3") (pintype "passive"))
      (node (ref "J1") (pin "GND") (pinfunction "GND_GND") (pintype "bidirectional"))
      (node (ref "J2") (pin "25") (pinfunction "25_25") (pintype "passive"))
      (node (ref "J2") (pin "26") (pinfunction "26_26") (pintype "passive"))
      (node (ref "J2") (pin "3") (pinfunction "3_3") (pintype "passive"))
      (node (ref "J2") (pin "4") (pinfunction "4_4") (pintype "passive"))
      (node (ref "JP1") (pin "6") (pinfunction "6_6") (pintype "bidirectional"))
      (node (ref "JP2") (pin "GND") (pinfunction "GND_GND") (pintype "bidirectional"))
      (node (ref "JP3") (pin "10") (pinfunction "10_10") (pintype "passive"))
      (node (ref "JP3") (pin "9") (pinfunction "9_9") (pintype "passive"))
      (node (ref "JP4") (pin "2") (pinfunction "2_2") (pintype "passive"))
      (node (ref "JP6") (pin "1") (pinfunction "1_1") (pintype "passive"))
      (node (ref "JP6") (pin "2") (pinfunction "2_2") (pintype "passive"))
      (node (ref "R1") (pin "1") (pinfunction "1_1") (pintype "passive"))
      (node (ref "R2") (pin "1") (pinfunction "1_1") (pintype "passive"))
      (node (ref "R8") (pin "2") (pinfunction "2_2") (pintype "passive"))
      (node (ref "Z1") (pin "1") (pinfunction "1_1") (pintype "passive"))
      (node (ref "Z2") (pin "1") (pinfunction "1_1") (pintype "passive"))
    )
    (net (code "48") (name "LATCH") (class "Default")
      (node (ref "CORE") (pin "5") (pinfunction "A7_5") (pintype "bidirectional"))
      (node (ref "IC1") (pin "4") (pinfunction "LE_4") (pintype "bidirectional"))
      (node (ref "IC2") (pin "4") (pinfunction "LE_4") (pintype "bidirectional"))
      (node (ref "IC3") (pin "40") (pinfunction "PF1(ADC1)_40") (pintype "bidirectional"))
      (node (ref "IC4") (pin "40") (pinfunction "PF1(ADC1)_40") (pintype "bidirectional"))
      (node (ref "J2") (pin "19") (pinfunction "19_19") (pintype "passive"))
    )
    (net (code "49") (name "Net-(CORE-RAW)") (class "Default")
      (node (ref "CORE") (pin "1") (pinfunction "RAW_1") (pintype "power_in"))
      (node (ref "D5") (pin "A") (pinfunction "A_A") (pintype "passive"))
    )
    (net (code "50") (name "Net-(D1-PadA)") (class "Default")
      (node (ref "D1") (pin "A") (pinfunction "A_A") (pintype "passive"))
      (node (ref "JP2") (pin "VBUS") (pinfunction "VBUS_VBUS") (pintype "bidirectional"))
    )
    (net (code "51") (name "Net-(D2-PadA)") (class "Default")
      (node (ref "D2") (pin "A") (pinfunction "A_A") (pintype "passive"))
      (node (ref "J1") (pin "PWR") (pinfunction "PWR_PWR") (pintype "bidirectional"))
    )
    (net (code "52") (name "Net-(D3-PadA)") (class "Default")
      (node (ref "D3") (pin "A") (pinfunction "A_A") (pintype "passive"))
      (node (ref "JP4") (pin "3") (pinfunction "3_3") (pintype "passive"))
    )
    (net (code "53") (name "Net-(IC1-REXT)") (class "Default")
      (node (ref "IC1") (pin "23") (pinfunction "REXT_23") (pintype "bidirectional"))
      (node (ref "R1") (pin "2") (pinfunction "2_2") (pintype "passive"))
    )
    (net (code "54") (name "Net-(IC2-REXT)") (class "Default")
      (node (ref "IC2") (pin "23") (pinfunction "REXT_23") (pintype "bidirectional"))
      (node (ref "R2") (pin "2") (pinfunction "2_2") (pintype "passive"))
    )
    (net (code "55") (name "Net-(IC5-SQW)") (class "Default")
      (node (ref "IC5") (pin "7") (pinfunction "SQW_7") (pintype "bidirectional"))
      (node (ref "R18") (pin "2") (pinfunction "2_2") (pintype "passive"))
      (node (ref "SJ1") (pin "2") (pinfunction "2_2") (pintype "passive"))
    )
    (net (code "56") (name "Net-(IC6-VO)") (class "Default")
      (node (ref "C12") (pin "1") (pinfunction "1_1") (pintype "passive"))
      (node (ref "D4") (pin "A") (pinfunction "A_A") (pintype "passive"))
      (node (ref "IC6") (pin "2") (pinfunction "VO_2") (pintype "passive"))
    )
    (net (code "57") (name "Net-(JP2-PadD+)") (class "Default")
      (node (ref "JP2") (pin "D+") (pinfunction "D+_D+") (pintype "bidirectional"))
      (node (ref "R4") (pin "1") (pinfunction "1_1") (pintype "passive"))
      (node (ref "Z1") (pin "2") (pinfunction "2_2") (pintype "passive"))
    )
    (net (code "58") (name "Net-(JP2-PadD-)") (class "Default")
      (node (ref "JP2") (pin "D-") (pinfunction "D-_D-") (pintype "bidirectional"))
      (node (ref "R3") (pin "1") (pinfunction "1_1") (pintype "passive"))
      (node (ref "Z2") (pin "2") (pinfunction "2_2") (pintype "passive"))
    )
    (net (code "59") (name "Net-(LED1-PadC)") (class "Default")
      (node (ref "LED1") (pin "C") (pinfunction "C_C") (pintype "passive"))
      (node (ref "R8") (pin "1") (pinfunction "1_1") (pintype "passive"))
    )
    (net (code "60") (name "Net-(T1-G)") (class "Default")
      (node (ref "R13") (pin "1") (pinfunction "1_1") (pintype "passive"))
      (node (ref "R7") (pin "2") (pinfunction "2_2") (pintype "passive"))
      (node (ref "T1") (pin "3") (pinfunction "G_3") (pintype "passive"))
    )
    (net (code "61") (name "Net-(T2-G)") (class "Default")
      (node (ref "R14") (pin "1") (pinfunction "1_1") (pintype "passive"))
      (node (ref "R9") (pin "2") (pinfunction "2_2") (pintype "passive"))
      (node (ref "T2") (pin "3") (pinfunction "G_3") (pintype "passive"))
    )
    (net (code "62") (name "Net-(T3-G)") (class "Default")
      (node (ref "R10") (pin "2") (pinfunction "2_2") (pintype "passive"))
      (node (ref "R15") (pin "1") (pinfunction "1_1") (pintype "passive"))
      (node (ref "T3") (pin "3") (pinfunction "G_3") (pintype "passive"))
    )
    (net (code "63") (name "Net-(T4-G)") (class "Default")
      (node (ref "R11") (pin "2") (pinfunction "2_2") (pintype "passive"))
      (node (ref "R16") (pin "1") (pinfunction "1_1") (pintype "passive"))
      (node (ref "T4") (pin "3") (pinfunction "G_3") (pintype "passive"))
    )
    (net (code "64") (name "Net-(T5-G)") (class "Default")
      (node (ref "R12") (pin "2") (pinfunction "2_2") (pintype "passive"))
      (node (ref "R17") (pin "1") (pinfunction "1_1") (pintype "passive"))
      (node (ref "T5") (pin "3") (pinfunction "G_3") (pintype "passive"))
    )
    (net (code "65") (name "PRESENCE") (class "Default")
      (node (ref "IC3") (pin "33") (pinfunction "PE2/~{HWB}_33") (pintype "bidirectional"))
      (node (ref "IC4") (pin "33") (pinfunction "PE2/~{HWB}_33") (pintype "bidirectional"))
      (node (ref "J2") (pin "23") (pinfunction "23_23") (pintype "passive"))
    )
    (net (code "66") (name "ROW0") (class "Default")
      (node (ref "SEG1") (pin "1") (pinfunction "COM_1") (pintype "bidirectional"))
      (node (ref "SEG1") (pin "11") (pinfunction "COM_11") (pintype "bidirectional"))
      (node (ref "T1") (pin "1") (pinfunction "D_1") (pintype "passive"))
    )
    (net (code "67") (name "ROW1") (class "Default")
      (node (ref "SEG2") (pin "1") (pinfunction "COM_1") (pintype "bidirectional"))
      (node (ref "SEG2") (pin "11") (pinfunction "COM_11") (pintype "bidirectional"))
      (node (ref "T2") (pin "1") (pinfunction "D_1") (pintype "passive"))
    )
    (net (code "68") (name "ROW2") (class "Default")
      (node (ref "SEG3") (pin "1") (pinfunction "COM_1") (pintype "bidirectional"))
      (node (ref "SEG3") (pin "11") (pinfunction "COM_11") (pintype "bidirectional"))
      (node (ref "T3") (pin "1") (pinfunction "D_1") (pintype "passive"))
    )
    (net (code "69") (name "ROW3") (class "Default")
      (node (ref "SEG4") (pin "1") (pinfunction "COM_1") (pintype "bidirectional"))
      (node (ref "SEG4") (pin "11") (pinfunction "COM_11") (pintype "bidirectional"))
      (node (ref "T4") (pin "1") (pinfunction "D_1") (pintype "passive"))
    )
    (net (code "70") (name "ROW4") (class "Default")
      (node (ref "SEG5") (pin "1") (pinfunction "COM_1") (pintype "bidirectional"))
      (node (ref "SEG5") (pin "11") (pinfunction "COM_11") (pintype "bidirectional"))
      (node (ref "T5") (pin "1") (pinfunction "D_1") (pintype "passive"))
    )
    (net (code "71") (name "RST") (class "Default")
      (node (ref "IC3") (pin "13") (pinfunction "~{RESET}_13") (pintype "bidirectional"))
      (node (ref "IC4") (pin "13") (pinfunction "~{RESET}_13") (pintype "bidirectional"))
      (node (ref "JP1") (pin "5") (pinfunction "5_5") (pintype "bidirectional"))
      (node (ref "R6") (pin "1") (pinfunction "1_1") (pintype "passive"))
    )
    (net (code "72") (name "SDO") (class "Default")
      (node (ref "IC1") (pin "22") (pinfunction "SDO_22") (pintype "bidirectional"))
      (node (ref "IC2") (pin "2") (pinfunction "SDI_2") (pintype "bidirectional"))
    )
    (net (code "73") (name "UCAP") (class "Default")
      (node (ref "C6") (pin "1") (pinfunction "1_1") (pintype "passive"))
      (node (ref "IC3") (pin "6") (pinfunction "UCAP_6") (pintype "bidirectional"))
      (node (ref "IC4") (pin "6") (pinfunction "UCAP_6") (pintype "bidirectional"))
    )
    (net (code "74") (name "USB_D+") (class "Default")
      (node (ref "IC3") (pin "4") (pinfunction "D+_4") (pintype "bidirectional"))
      (node (ref "IC4") (pin "4") (pinfunction "D+_4") (pintype "bidirectional"))
      (node (ref "R4") (pin "2") (pinfunction "2_2") (pintype "passive"))
    )
    (net (code "75") (name "USB_D-") (class "Default")
      (node (ref "IC3") (pin "3") (pinfunction "D-_3") (pintype "bidirectional"))
      (node (ref "IC4") (pin "3") (pinfunction "D-_3") (pintype "bidirectional"))
      (node (ref "R3") (pin "2") (pinfunction "2_2") (pintype "passive"))
    )
    (net (code "76") (name "VCC5V") (class "Default")
      (node (ref "C1") (pin "1") (pinfunction "1_1") (pintype "passive"))
      (node (ref "C2") (pin "1") (pinfunction "1_1") (pintype "passive"))
      (node (ref "C8") (pin "1") (pinfunction "1_1") (pintype "passive"))
      (node (ref "C9") (pin "1") (pinfunction "1_1") (pintype "passive"))
      (node (ref "D1") (pin "C") (pinfunction "C_C") (pintype "passive"))
      (node (ref "D4") (pin "C") (pinfunction "C_C") (pintype "passive"))
      (node (ref "D5") (pin "C") (pinfunction "C_C") (pintype "passive"))
      (node (ref "IC1") (pin "24") (pinfunction "VDD_24") (pintype "bidirectional"))
      (node (ref "IC2") (pin "24") (pinfunction "VDD_24") (pintype "bidirectional"))
      (node (ref "IC3") (pin "14") (pinfunction "VCC_14") (pintype "bidirectional"))
      (node (ref "IC3") (pin "2") (pinfunction "UVCC_2") (pintype "bidirectional"))
      (node (ref "IC3") (pin "34") (pinfunction "VCC_34") (pintype "bidirectional"))
      (node (ref "IC3") (pin "7") (pinfunction "VBUS_7") (pintype "bidirectional"))
      (node (ref "IC4") (pin "14") (pinfunction "VCC_14") (pintype "bidirectional"))
      (node (ref "IC4") (pin "2") (pinfunction "UVCC_2") (pintype "bidirectional"))
      (node (ref "IC4") (pin "34") (pinfunction "VCC_34") (pintype "bidirectional"))
      (node (ref "IC4") (pin "7") (pinfunction "VBUS_7") (pintype "bidirectional"))
      (node (ref "IC5") (pin "2") (pinfunction "VCC_2") (pintype "bidirectional"))
      (node (ref "J2") (pin "1") (pinfunction "1_1") (pintype "passive"))
      (node (ref "J2") (pin "2") (pinfunction "2_2") (pintype "passive"))
      (node (ref "JP1") (pin "2") (pinfunction "2_2") (pintype "bidirectional"))
      (node (ref "JP3") (pin "1") (pinfunction "1_1") (pintype "passive"))
      (node (ref "JP4") (pin "1") (pinfunction "1_1") (pintype "passive"))
      (node (ref "JP6") (pin "10") (pinfunction "10_10") (pintype "passive"))
      (node (ref "L1") (pin "1") (pinfunction "1_1") (pintype "passive"))
      (node (ref "R18") (pin "1") (pinfunction "1_1") (pintype "passive"))
      (node (ref "R19") (pin "2") (pinfunction "2_2") (pintype "passive"))
      (node (ref "R6") (pin "2") (pinfunction "2_2") (pintype "passive"))
    )
    (net (code "77") (name "VCC9V") (class "Default")
      (node (ref "C11") (pin "1") (pinfunction "1_1") (pintype "passive"))
      (node (ref "D2") (pin "C") (pinfunction "C_C") (pintype "passive"))
      (node (ref "D3") (pin "C") (pinfunction "C_C") (pintype "passive"))
      (node (ref "IC6") (pin "1") (pinfunction "VI_1") (pintype "input"))
      (node (ref "JP3") (pin "2") (pinfunction "2_2") (pintype "passive"))
      (node (ref "JP6") (pin "9") (pinfunction "9_9") (pintype "passive"))
      (node (ref "R13") (pin "2") (pinfunction "2_2") (pintype "passive"))
      (node (ref "R14") (pin "2") (pinfunction "2_2") (pintype "passive"))
      (node (ref "R15") (pin "2") (pinfunction "2_2") (pintype "passive"))
      (node (ref "R16") (pin "2") (pinfunction "2_2") (pintype "passive"))
      (node (ref "R17") (pin "2") (pinfunction "2_2") (pintype "passive"))
      (node (ref "T1") (pin "2") (pinfunction "S_2") (pintype "passive"))
      (node (ref "T2") (pin "2") (pinfunction "S_2") (pintype "passive"))
      (node (ref "T3") (pin "2") (pinfunction "S_2") (pintype "passive"))
      (node (ref "T4") (pin "2") (pinfunction "S_2") (pintype "passive"))
      (node (ref "T5") (pin "2") (pinfunction "S_2") (pintype "passive"))
    )
    (net (code "78") (name "XTAL1") (class "Default")
      (node (ref "C4") (pin "2") (pinfunction "2_2") (pintype "passive"))
      (node (ref "IC3") (pin "17") (pinfunction "XTAL1_17") (pintype "bidirectional"))
      (node (ref "IC4") (pin "17") (pinfunction "XTAL1_17") (pintype "bidirectional"))
      (node (ref "R5") (pin "2") (pinfunction "2_2") (pintype "passive"))
      (node (ref "X1") (pin "2") (pinfunction "P$2_2") (pintype "bidirectional"))
    )
    (net (code "79") (name "XTAL2") (class "Default")
      (node (ref "C5") (pin "2") (pinfunction "2_2") (pintype "passive"))
      (node (ref "IC3") (pin "16") (pinfunction "XTAL2_16") (pintype "bidirectional"))
      (node (ref "IC4") (pin "16") (pinfunction "XTAL2_16") (pintype "bidirectional"))
      (node (ref "R5") (pin "1") (pinfunction "1_1") (pintype "passive"))
      (node (ref "X1") (pin "1") (pinfunction "P$1_1") (pintype "bidirectional"))
    )
    (net (code "80") (name "unconnected-(CORE-~{RST}-Pad23)") (class "Default")
      (node (ref "CORE") (pin "23") (pinfunction "~{RST}_23") (pintype "bidirectional"))
    )
    (net (code "81") (name "unconnected-(IC1-OUT10-Pad15)") (class "Default")
      (node (ref "IC1") (pin "15") (pinfunction "OUT10_15") (pintype "bidirectional"))
    )
    (net (code "82") (name "unconnected-(IC1-OUT11-Pad16)") (class "Default")
      (node (ref "IC1") (pin "16") (pinfunction "OUT11_16") (pintype "bidirectional"))
    )
    (net (code "83") (name "unconnected-(IC1-OUT12-Pad17)") (class "Default")
      (node (ref "IC1") (pin "17") (pinfunction "OUT12_17") (pintype "bidirectional"))
    )
    (net (code "84") (name "unconnected-(IC1-OUT13-Pad18)") (class "Default")
      (node (ref "IC1") (pin "18") (pinfunction "OUT13_18") (pintype "bidirectional"))
    )
    (net (code "85") (name "unconnected-(IC1-OUT14-Pad19)") (class "Default")
      (node (ref "IC1") (pin "19") (pinfunction "OUT14_19") (pintype "bidirectional"))
    )
    (net (code "86") (name "unconnected-(IC1-OUT15-Pad20)") (class "Default")
      (node (ref "IC1") (pin "20") (pinfunction "OUT15_20") (pintype "bidirectional"))
    )
    (net (code "87") (name "unconnected-(IC2-OUT8-Pad13)") (class "Default")
      (node (ref "IC2") (pin "13") (pinfunction "OUT8_13") (pintype "bidirectional"))
    )
    (net (code "88") (name "unconnected-(IC2-OUT9-Pad14)") (class "Default")
      (node (ref "IC2") (pin "14") (pinfunction "OUT9_14") (pintype "bidirectional"))
    )
    (net (code "89") (name "unconnected-(IC2-OUT10-Pad15)") (class "Default")
      (node (ref "IC2") (pin "15") (pinfunction "OUT10_15") (pintype "bidirectional"))
    )
    (net (code "90") (name "unconnected-(IC2-OUT11-Pad16)") (class "Default")
      (node (ref "IC2") (pin "16") (pinfunction "OUT11_16") (pintype "bidirectional"))
    )
    (net (code "91") (name "unconnected-(IC2-OUT12-Pad17)") (class "Default")
      (node (ref "IC2") (pin "17") (pinfunction "OUT12_17") (pintype "bidirectional"))
    )
    (net (code "92") (name "unconnected-(IC2-OUT13-Pad18)") (class "Default")
      (node (ref "IC2") (pin "18") (pinfunction "OUT13_18") (pintype "bidirectional"))
    )
    (net (code "93") (name "unconnected-(IC2-OUT14-Pad19)") (class "Default")
      (node (ref "IC2") (pin "19") (pinfunction "OUT14_19") (pintype "bidirectional"))
    )
    (net (code "94") (name "unconnected-(IC2-OUT15-Pad20)") (class "Default")
      (node (ref "IC2") (pin "20") (pinfunction "OUT15_20") (pintype "bidirectional"))
    )
    (net (code "95") (name "unconnected-(IC2-SDO-Pad22)") (class "Default")
      (node (ref "IC2") (pin "22") (pinfunction "SDO_22") (pintype "bidirectional"))
    )
    (net (code "96") (name "unconnected-(IC5-32K-Pad6)") (class "Default")
      (node (ref "IC5") (pin "6") (pinfunction "32K_6") (pintype "bidirectional"))
    )
    (net (code "97") (name "unconnected-(IC5-BAT-Pad5)") (class "Default")
      (node (ref "IC5") (pin "5") (pinfunction "BAT_5") (pintype "bidirectional"))
    )
    (net (code "98") (name "unconnected-(IC5-RST-Pad8)") (class "Default")
      (node (ref "IC5") (pin "8") (pinfunction "RST_8") (pintype "bidirectional"))
    )
    (net (code "99") (name "unconnected-(J1-PadGNDBREAK)") (class "Default")
      (node (ref "J1") (pin "GNDBREAK") (pinfunction "GNDBREAK_GNDBREAK") (pintype "bidirectional"))
    )
    (net (code "100") (name "unconnected-(J2-Pad18)") (class "Default")
      (node (ref "J2") (pin "18") (pinfunction "18_18") (pintype "passive"))
    )
  )
)
